# CAT-PTT.net
KiCad netlist of a schematic drawn in Altium Designer
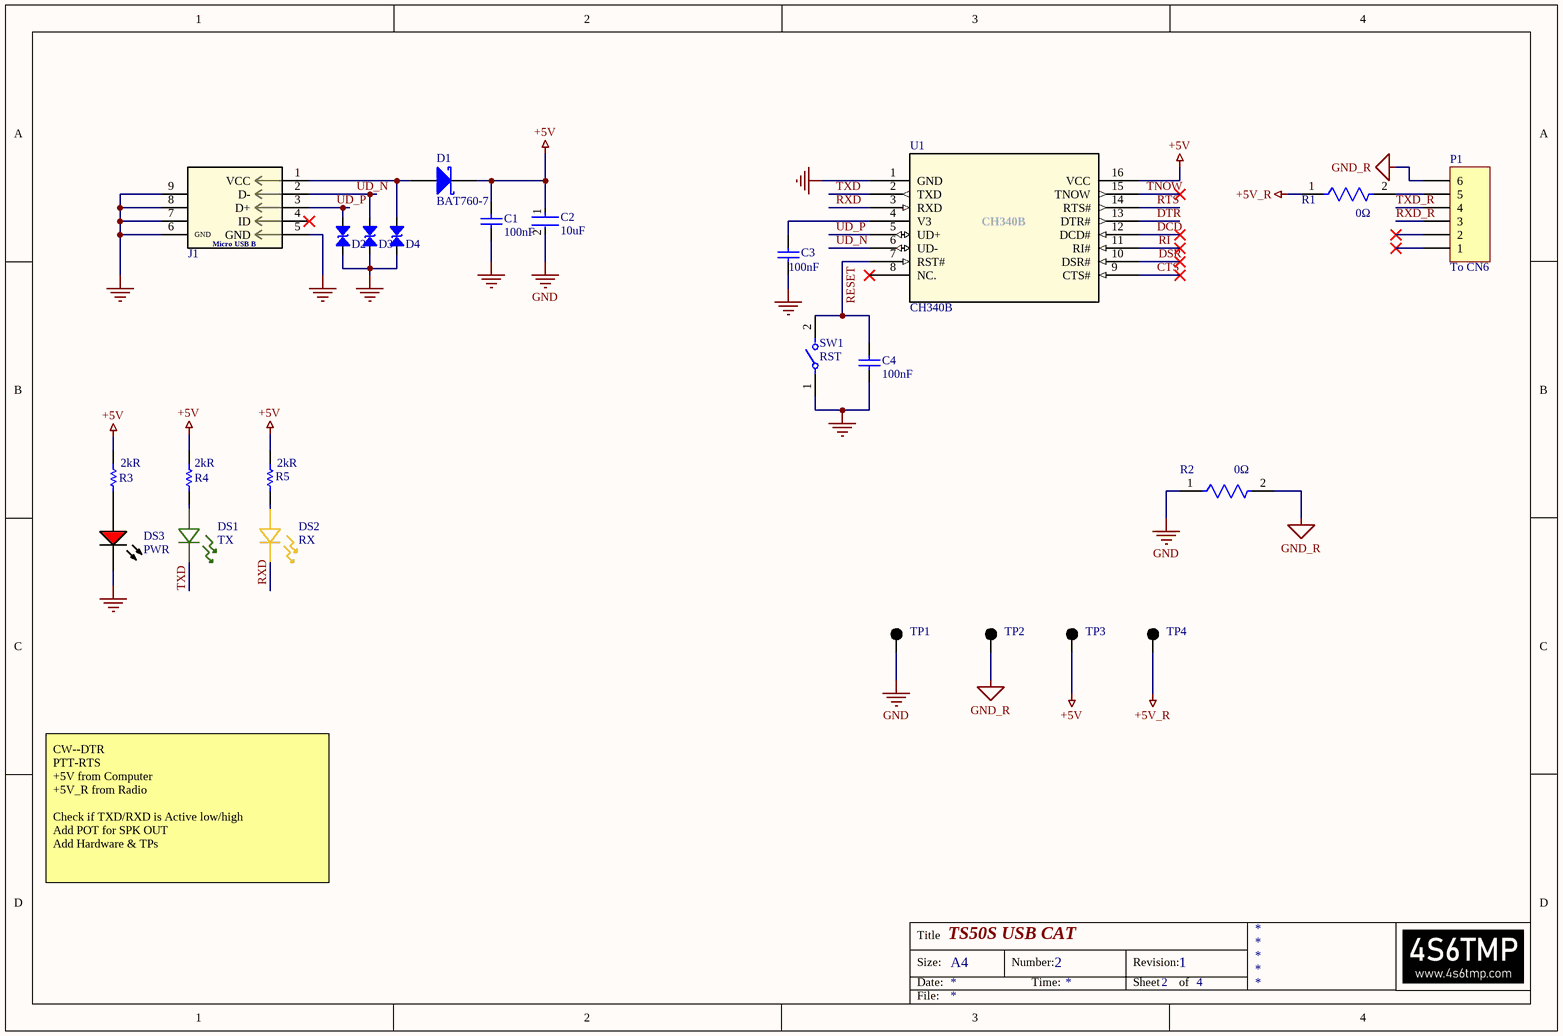
[diagram p0: CAT-PTT.SchDoc]

(export (version "E")
  (design (tool "Eeschema 10.0.6"))
  (components
    (comp (ref "C1")
      (value "100nF")
      (footprint "CAPC1608X90X35ML10T15")
      (description "Chip Capacitor, 100 nF, +/- 10%, 50 V, -55 to 125 degC, 0603 (1608 Metric), RoHS, Tape and Reel")
      (fields
        (field (name "MANUFACTURER") "Murata")
        (field (name "MANUFACTURER PART NUMBER") "GCM188R71H104KA57D")
      )
      (libsource (lib "Altium Content Vault") (part "CAP-NP-2"))
    )
    (comp (ref "C2")
      (value "10uF")
      (footprint "FP-GRM188-0_1-e0_2_0_55-IPC_A")
      (description "Chip Multilayer Ceramic Capacitors for General Purpose, 0603, 10uF, X5R, 15%, 20%, 6.3V")
      (fields (field (name "VOLTAGE") "6.3V") (field (name "TOLERANCE") "20%"))
      (libsource (lib "Altium Content Vault") (part "02cd4be3c70576c341d710602a673aa"))
    )
    (comp (ref "C3")
      (value "100nF")
      (footprint "CAPC1608X90X35ML10T15")
      (description "Chip Capacitor, 100 nF, +/- 10%, 50 V, -55 to 125 degC, 0603 (1608 Metric), RoHS, Tape and Reel")
      (fields
        (field (name "MANUFACTURER") "Murata")
        (field (name "MANUFACTURER PART NUMBER") "GCM188R71H104KA57D")
      )
      (libsource (lib "Altium Content Vault") (part "CAP-NP-2"))
    )
    (comp (ref "C4")
      (value "100nF")
      (footprint "CAPC1608X90X35ML10T15")
      (description "Chip Capacitor, 100 nF, +/- 10%, 50 V, -55 to 125 degC, 0603 (1608 Metric), RoHS, Tape and Reel")
      (fields
        (field (name "MANUFACTURER") "Murata")
        (field (name "MANUFACTURER PART NUMBER") "GCM188R71H104KA57D")
      )
      (libsource (lib "Altium Content Vault") (part "CAP-NP-2"))
    )
    (comp (ref "D1")
      (value "BAT760-7")
      (footprint "SOD323_DIO")
      (description "30V 1A 550mV @ 1A SOD-323 Schottky Barrier Diodes (SBD) RoHS")
      (libsource (lib "BAT760-7") (part "BAT760-7"))
    )
    (comp (ref "D2")
      (value "ESD Diode")
      (footprint "0603ESDA-05N")
      (description "Bidirectional - 50V - 5V 0603 ESD Protection Devices ROHS")
      (libsource (lib "0603ESDA-05N") (part "0603ESDA-05N"))
    )
    (comp (ref "D3")
      (value "ESD Diode")
      (footprint "0603ESDA-05N")
      (description "Bidirectional - 50V - 5V 0603 ESD Protection Devices ROHS")
      (libsource (lib "0603ESDA-05N") (part "0603ESDA-05N"))
    )
    (comp (ref "D4")
      (value "ESD Diode")
      (footprint "0603ESDA-05N")
      (description "Bidirectional - 50V - 5V 0603 ESD Protection Devices ROHS")
      (libsource (lib "0603ESDA-05N") (part "0603ESDA-05N"))
    )
    (comp (ref "DS1")
      (value "TX")
      (footprint "LED_19-217/GHC-YR1S2/3T_EVE")
      (description "No Description Available")
      (fields
        (field (name "MANUFACTURER_PART_NUMBER") "19-217/GHC-YR1S2/3T")
        (field (name "COPYRIGHT") "Copyright (C) 2018 Accelerated Designs. All rights reserved")
      )
      (libsource (lib "19-217GHC-YR1S23T") (part "19-217/GHC-YR1S2/3T"))
    )
    (comp (ref "DS2")
      (value "RX")
      (footprint "LED_19-217/GHC-YR1S2/3T_EVE")
      (description "Yellow 590nm LED Indication - Discrete 2V 0603 (1608 Metric)")
      (fields (field (name "MANUFACTURER_PART_NUMBER") "19-217/Y5C-AP1Q2/3T"))
      (libsource (lib "19-217Y5C-AP1Q2-3T") (part "19-217/Y5C-AP1Q2/3T"))
    )
    (comp (ref "DS3")
      (value "PWR")
      (footprint "EVRL-0603-2_V")
      (description "Chip LED, Red, 5 V, 25 mA, -40 to 85 degC, 2-Pin SMD (0603), RoHS, Tape and Reel")
      (fields (field (name "MANUFACTURER") "Everlight Electronics"))
      (libsource (lib "Altium Content Vault") (part "LED-RED-AK-2"))
    )
    (comp (ref "J1")
      (value "U254-051N-4BH806")
      (footprint "CONN_10103594-0001LF_AMP")
      (description "USB - Micro B Female USB 2 5 SMD USB Connectors RoHS")
      (libsource (lib "U254-051N-4BH806") (part "U254-051N-4BH806"))
    )
    (comp (ref "P1")
      (value "To CN6")
      (footprint "HDR1X6")
      (description "Header, 6-Pin")
      (fields (field (name "PUBLISHER") "Altium Limited"))
      (libsource (lib "Miscellaneous Connectors") (part "Header 6"))
    )
    (comp (ref "R1")
      (value "0Ω")
      (footprint "FP-RC0603-MFG")
      (description "RES SMD 0 OHM JUMPER 1/10W 0603")
      (fields
        (field (name "TOLERANCE") "1%")
        (field (name "OCTOPART") "https://octopart.com/rc0603fr-070rl-yageo-1180803")
      )
      (libsource (lib "Altium Content Vault") (part "1029c3af85768c4190bb7ad29bc67b5"))
    )
    (comp (ref "R2")
      (value "0Ω")
      (footprint "FP-RC0603-MFG")
      (description "DNP")
      (fields
        (field (name "TOLERANCE") "1%")
        (field (name "OCTOPART") "https://octopart.com/rc0603fr-070rl-yageo-1180803")
      )
      (libsource (lib "Altium Content Vault") (part "1029c3af85768c4190bb7ad29bc67b5"))
    )
    (comp (ref "R3")
      (value "2kR")
      (footprint "RESC1608X55X25NL10T15")
      (fields
        (field (name "PART NUMBER") "RC0603JR-072KL")
        (field (name "MANUFACTURER") "Yageo")
        (field (name "TOLERANCE") "5%")
      )
      (libsource (lib "Altium Content Vault") (part "RES"))
    )
    (comp (ref "R4")
      (value "2kR")
      (footprint "RESC1608X55X25NL10T15")
      (fields
        (field (name "PART NUMBER") "RC0603JR-072KL")
        (field (name "MANUFACTURER") "Yageo")
        (field (name "TOLERANCE") "5%")
      )
      (libsource (lib "Altium Content Vault") (part "RES"))
    )
    (comp (ref "R5")
      (value "2kR")
      (footprint "RESC1608X55X25NL10T15")
      (fields
        (field (name "PART NUMBER") "RC0603JR-072KL")
        (field (name "MANUFACTURER") "Yageo")
        (field (name "TOLERANCE") "5%")
      )
      (libsource (lib "Altium Content Vault") (part "RES"))
    )
    (comp (ref "SW1")
      (value "RST")
      (footprint "FP-B3U-1000P-B-MFG")
      (description "SWITCH TACTILE SPST-NO 0.05A 12V")
      (fields
        (field (name "MANUFACTURER PART NUMBER") "B3U-1000P-B")
        (field (name "OCTOPART") "https://octopart.com/b3u-1000p-b-omron-1057356")
      )
      (libsource (lib "Altium Content Vault") (part "bb27bde45df87f1f469753f287ef5ae"))
    )
    (comp (ref "TP1")
      (value "GND")
      (footprint "KSTN-5001")
      (description "Test Point, Black, 1-Pin THD, RoHS, Bulk")
      (fields (field (name "MANUFACTURER") "Keystone"))
      (libsource (lib "Altium Content Vault") (part "KSTN-TP-5001"))
    )
    (comp (ref "TP2")
      (value "GND_R")
      (footprint "KSTN-5001")
      (description "Test Point, Black, 1-Pin THD, RoHS, Bulk")
      (fields (field (name "MANUFACTURER") "Keystone"))
      (libsource (lib "Altium Content Vault") (part "KSTN-TP-5001"))
    )
    (comp (ref "TP3")
      (value "+5V")
      (footprint "KSTN-5001")
      (description "Test Point, Black, 1-Pin THD, RoHS, Bulk")
      (fields (field (name "MANUFACTURER") "Keystone"))
      (libsource (lib "Altium Content Vault") (part "KSTN-TP-5001"))
    )
    (comp (ref "TP4")
      (value "+5V_R")
      (footprint "KSTN-5001")
      (description "Test Point, Black, 1-Pin THD, RoHS, Bulk")
      (fields (field (name "MANUFACTURER") "Keystone"))
      (libsource (lib "Altium Content Vault") (part "KSTN-TP-5001"))
    )
    (comp (ref "U1")
      (value "CH340B")
      (footprint "SOIC-16")
      (description "Transceiver USB 2.0 2Mbps SOP-16_150mil USB ICs RoHS")
      (libsource (lib "CH340B") (part "CH340B"))
    )
  )
  (nets
    (net (code "1") (name "+5V") (class "Default")
      (node (ref "C1") (pin "2") (pinfunction "2_2") (pintype "passive"))
      (node (ref "C2") (pin "1") (pinfunction "1_1") (pintype "passive"))
      (node (ref "D1") (pin "1") (pinfunction "K_1") (pintype "passive"))
      (node (ref "R3") (pin "2") (pinfunction "2_2") (pintype "passive"))
      (node (ref "R4") (pin "2") (pinfunction "2_2") (pintype "passive"))
      (node (ref "R5") (pin "2") (pinfunction "2_2") (pintype "passive"))
      (node (ref "TP3") (pin "1") (pintype "passive"))
      (node (ref "U1") (pin "16") (pinfunction "VCC_16") (pintype "power_in"))
    )
    (net (code "2") (name "+5V_R") (class "Default")
      (node (ref "R1") (pin "1") (pinfunction "1_1") (pintype "passive"))
      (node (ref "TP4") (pin "1") (pintype "passive"))
    )
    (net (code "3") (name "/CTS") (class "Default")
      (node (ref "U1") (pin "9") (pinfunction "CTS#_9") (pintype "input+no_connect"))
    )
    (net (code "4") (name "/DCD") (class "Default")
      (node (ref "U1") (pin "12") (pinfunction "DCD#_12") (pintype "input+no_connect"))
    )
    (net (code "5") (name "/DSR") (class "Default")
      (node (ref "U1") (pin "10") (pinfunction "DSR#_10") (pintype "input+no_connect"))
    )
    (net (code "6") (name "/DTR") (class "Default")
      (node (ref "U1") (pin "13") (pinfunction "DTR#_13") (pintype "output"))
    )
    (net (code "7") (name "/RESET") (class "Default")
      (node (ref "C4") (pin "2") (pinfunction "2_2") (pintype "passive"))
      (node (ref "SW1") (pin "2") (pinfunction "2_2") (pintype "passive"))
      (node (ref "U1") (pin "7") (pinfunction "RST#_7") (pintype "input"))
    )
    (net (code "8") (name "/RI") (class "Default")
      (node (ref "U1") (pin "11") (pinfunction "RI#_11") (pintype "input+no_connect"))
    )
    (net (code "9") (name "/RTS") (class "Default")
      (node (ref "U1") (pin "14") (pinfunction "RTS#_14") (pintype "output"))
    )
    (net (code "10") (name "/RXD") (class "Default")
      (node (ref "DS2") (pin "1") (pinfunction "1_1") (pintype "passive"))
      (node (ref "U1") (pin "3") (pinfunction "RXD_3") (pintype "input"))
    )
    (net (code "11") (name "/RXD_R") (class "Default")
      (node (ref "P1") (pin "3") (pinfunction "3_3") (pintype "passive"))
    )
    (net (code "12") (name "/TNOW") (class "Default")
      (node (ref "U1") (pin "15") (pinfunction "TNOW_15") (pintype "output+no_connect"))
    )
    (net (code "13") (name "/TXD") (class "Default")
      (node (ref "DS1") (pin "1") (pinfunction "1_1") (pintype "passive"))
      (node (ref "U1") (pin "2") (pinfunction "TXD_2") (pintype "output"))
    )
    (net (code "14") (name "/TXD_R") (class "Default")
      (node (ref "P1") (pin "4") (pinfunction "4_4") (pintype "passive"))
    )
    (net (code "15") (name "/UD_N") (class "Default")
      (node (ref "D3") (pin "1") (pinfunction "1_1") (pintype "passive"))
      (node (ref "J1") (pin "2") (pinfunction "D-_2") (pintype "passive"))
      (node (ref "U1") (pin "6") (pinfunction "UD-_6") (pintype "bidirectional"))
    )
    (net (code "16") (name "/UD_P") (class "Default")
      (node (ref "D2") (pin "1") (pinfunction "1_1") (pintype "passive"))
      (node (ref "J1") (pin "3") (pinfunction "D+_3") (pintype "passive"))
      (node (ref "U1") (pin "5") (pinfunction "UD+_5") (pintype "bidirectional"))
    )
    (net (code "17") (name "GND") (class "Default")
      (node (ref "C1") (pin "1") (pinfunction "1_1") (pintype "passive"))
      (node (ref "C2") (pin "2") (pinfunction "2_2") (pintype "passive"))
      (node (ref "C3") (pin "2") (pinfunction "2_2") (pintype "passive"))
      (node (ref "C4") (pin "1") (pinfunction "1_1") (pintype "passive"))
      (node (ref "D2") (pin "2") (pinfunction "2_2") (pintype "passive"))
      (node (ref "D3") (pin "2") (pinfunction "2_2") (pintype "passive"))
      (node (ref "D4") (pin "2") (pinfunction "2_2") (pintype "passive"))
      (node (ref "DS3") (pin "2") (pinfunction "K_2") (pintype "passive"))
      (node (ref "J1") (pin "5") (pinfunction "GND_5") (pintype "power_in"))
      (node (ref "J1") (pin "6") (pinfunction "GND_6") (pintype "power_in"))
      (node (ref "J1") (pin "7") (pinfunction "GND_7") (pintype "power_in"))
      (node (ref "J1") (pin "8") (pinfunction "GND_8") (pintype "power_in"))
      (node (ref "J1") (pin "9") (pinfunction "GND_9") (pintype "power_in"))
      (node (ref "R2") (pin "1") (pinfunction "1_1") (pintype "passive"))
      (node (ref "SW1") (pin "1") (pinfunction "1_1") (pintype "passive"))
      (node (ref "TP1") (pin "1") (pintype "passive"))
      (node (ref "U1") (pin "1") (pinfunction "GND_1") (pintype "passive"))
    )
    (net (code "18") (name "GND_R") (class "Default")
      (node (ref "P1") (pin "6") (pinfunction "6_6") (pintype "passive"))
      (node (ref "R2") (pin "2") (pinfunction "2_2") (pintype "passive"))
      (node (ref "TP2") (pin "1") (pintype "passive"))
    )
    (net (code "19") (name "Net-(D1-A)") (class "Default")
      (node (ref "D1") (pin "2") (pinfunction "A_2") (pintype "passive"))
      (node (ref "D4") (pin "1") (pinfunction "1_1") (pintype "passive"))
      (node (ref "J1") (pin "1") (pinfunction "VCC_1") (pintype "power_in"))
    )
    (net (code "20") (name "Net-(DS1-Pad2)") (class "Default")
      (node (ref "DS1") (pin "2") (pinfunction "2_2") (pintype "passive"))
      (node (ref "R4") (pin "1") (pinfunction "1_1") (pintype "passive"))
    )
    (net (code "21") (name "Net-(DS2-Pad2)") (class "Default")
      (node (ref "DS2") (pin "2") (pinfunction "2_2") (pintype "passive"))
      (node (ref "R5") (pin "1") (pinfunction "1_1") (pintype "passive"))
    )
    (net (code "22") (name "Net-(DS3-A)") (class "Default")
      (node (ref "DS3") (pin "1") (pinfunction "A_1") (pintype "passive"))
      (node (ref "R3") (pin "1") (pinfunction "1_1") (pintype "passive"))
    )
    (net (code "23") (name "Net-(P1-Pad5)") (class "Default")
      (node (ref "P1") (pin "5") (pinfunction "5_5") (pintype "passive"))
      (node (ref "R1") (pin "2") (pinfunction "2_2") (pintype "passive"))
    )
    (net (code "24") (name "Net-(U1-V3)") (class "Default")
      (node (ref "C3") (pin "1") (pinfunction "1_1") (pintype "passive"))
      (node (ref "U1") (pin "4") (pinfunction "V3_4") (pintype "power_in"))
    )
    (net (code "25") (name "unconnected-(J1-ID-Pad4)") (class "Default")
      (node (ref "J1") (pin "4") (pinfunction "ID_4") (pintype "passive+no_connect"))
    )
    (net (code "26") (name "unconnected-(P1-Pad1)") (class "Default")
      (node (ref "P1") (pin "1") (pinfunction "1_1") (pintype "passive+no_connect"))
    )
    (net (code "27") (name "unconnected-(P1-Pad2)") (class "Default")
      (node (ref "P1") (pin "2") (pinfunction "2_2") (pintype "passive+no_connect"))
    )
    (net (code "28") (name "unconnected-(U1-NC.-Pad8)") (class "Default")
      (node (ref "U1") (pin "8") (pinfunction "NC._8") (pintype "passive+no_connect"))
    )
  )
)
